# LightBox.net
KiCad netlist of a schematic drawn in EAGLE
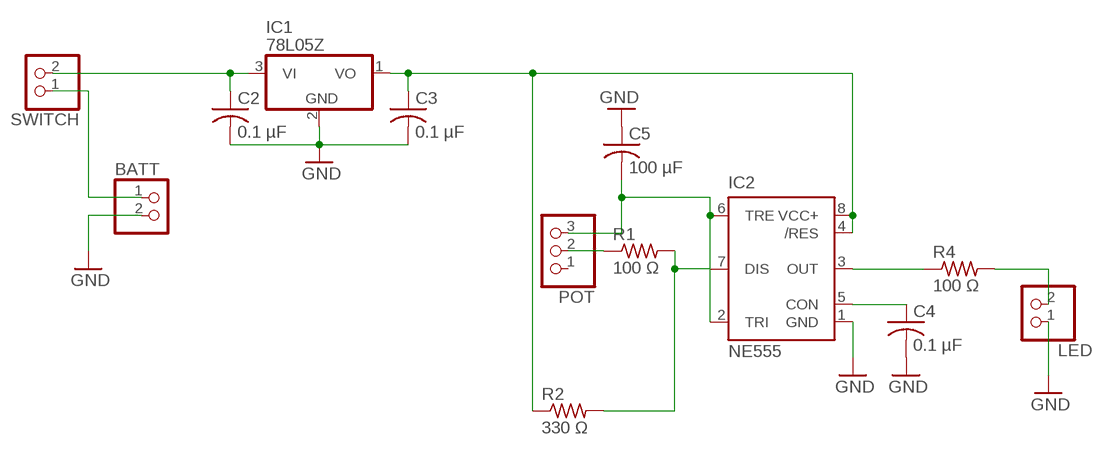
[diagram p0: schematic, sheet 1]

(export (version "E")
  (design (tool "Eeschema 10.0.6"))
  (components
    (comp (ref "BATT")
      (value "PINHD-1X2")
      (footprint "eagle-import:1X02")
      (libsource (lib "eagle-import") (part "PINHD-1X2"))
    )
    (comp (ref "C2")
      (value "0.1 µF")
      (footprint "eagle-import:C0805")
      (libsource (lib "eagle-import") (part "C-USC0805"))
    )
    (comp (ref "C3")
      (value "0.1 µF")
      (footprint "eagle-import:C0805")
      (libsource (lib "eagle-import") (part "C-USC0805"))
    )
    (comp (ref "C4")
      (value "0.1 µF")
      (footprint "eagle-import:C0805")
      (libsource (lib "eagle-import") (part "C-USC0805"))
    )
    (comp (ref "C5")
      (value "100 µF")
      (footprint "eagle-import:C025-024X044")
      (libsource (lib "eagle-import") (part "C-US025-024X044"))
    )
    (comp (ref "IC1")
      (value "78L05Z")
      (footprint "eagle-import:TO92")
      (libsource (lib "eagle-import") (part "78ZL05"))
    )
    (comp (ref "IC2")
      (value "NE555")
      (footprint "eagle-import:DIL-08")
      (fields (field (name "MF") "Arrow Electronics") (field (name "MPN") "NE555N"))
      (libsource (lib "eagle-import") (part "NE555"))
    )
    (comp (ref "LED")
      (value "PINHD-1X2")
      (footprint "eagle-import:1X02")
      (libsource (lib "eagle-import") (part "PINHD-1X2"))
    )
    (comp (ref "POT")
      (value "PINHD-1X3")
      (footprint "eagle-import:1X03")
      (libsource (lib "eagle-import") (part "PINHD-1X3"))
    )
    (comp (ref "R1")
      (value "100 Ω")
      (footprint "eagle-import:R0805")
      (libsource (lib "eagle-import") (part "R-US_R0805"))
    )
    (comp (ref "R2")
      (value "330 Ω")
      (footprint "eagle-import:R0805")
      (libsource (lib "eagle-import") (part "R-US_R0805"))
    )
    (comp (ref "R4")
      (value "100 Ω")
      (footprint "eagle-import:R0805")
      (libsource (lib "eagle-import") (part "R-US_R0805"))
    )
    (comp (ref "SWITCH")
      (value "PINHD-1X2")
      (footprint "eagle-import:1X02")
      (libsource (lib "eagle-import") (part "PINHD-1X2"))
    )
  )
  (nets
    (net (code "1") (name "GND") (class "Default")
      (node (ref "BATT") (pin "2") (pinfunction "2_2") (pintype "passive"))
      (node (ref "C2") (pin "2") (pinfunction "2_2") (pintype "passive"))
      (node (ref "C3") (pin "2") (pinfunction "2_2") (pintype "passive"))
      (node (ref "C4") (pin "2") (pinfunction "2_2") (pintype "passive"))
      (node (ref "C5") (pin "1") (pinfunction "1_1") (pintype "passive"))
      (node (ref "IC1") (pin "2") (pinfunction "GND_2") (pintype "passive"))
      (node (ref "IC2") (pin "1") (pinfunction "GND_1") (pintype "power_in"))
      (node (ref "LED") (pin "1") (pinfunction "1_1") (pintype "passive"))
    )
    (net (code "2") (name "Net-(BATT-Pad1)") (class "Default")
      (node (ref "BATT") (pin "1") (pinfunction "1_1") (pintype "passive"))
      (node (ref "SWITCH") (pin "1") (pinfunction "1_1") (pintype "passive"))
    )
    (net (code "3") (name "Net-(IC1-VI)") (class "Default")
      (node (ref "C2") (pin "1") (pinfunction "1_1") (pintype "passive"))
      (node (ref "IC1") (pin "3") (pinfunction "VI_3") (pintype "input"))
      (node (ref "SWITCH") (pin "2") (pinfunction "2_2") (pintype "passive"))
    )
    (net (code "4") (name "Net-(IC1-VO)") (class "Default")
      (node (ref "C3") (pin "1") (pinfunction "1_1") (pintype "passive"))
      (node (ref "IC1") (pin "1") (pinfunction "VO_1") (pintype "passive"))
      (node (ref "IC2") (pin "4") (pinfunction "/RES_4") (pintype "input"))
      (node (ref "IC2") (pin "8") (pinfunction "VCC+_8") (pintype "power_in"))
      (node (ref "R2") (pin "1") (pinfunction "1_1") (pintype "passive"))
    )
    (net (code "5") (name "Net-(IC2-CON)") (class "Default")
      (node (ref "C4") (pin "1") (pinfunction "1_1") (pintype "passive"))
      (node (ref "IC2") (pin "5") (pinfunction "CON_5") (pintype "input"))
    )
    (net (code "6") (name "Net-(IC2-DIS)") (class "Default")
      (node (ref "IC2") (pin "7") (pinfunction "DIS_7") (pintype "input"))
      (node (ref "R1") (pin "2") (pinfunction "2_2") (pintype "passive"))
      (node (ref "R2") (pin "2") (pinfunction "2_2") (pintype "passive"))
    )
    (net (code "7") (name "Net-(IC2-OUT)") (class "Default")
      (node (ref "IC2") (pin "3") (pinfunction "OUT_3") (pintype "output"))
      (node (ref "R4") (pin "1") (pinfunction "1_1") (pintype "passive"))
    )
    (net (code "8") (name "Net-(IC2-TRE)") (class "Default")
      (node (ref "C5") (pin "2") (pinfunction "2_2") (pintype "passive"))
      (node (ref "IC2") (pin "2") (pinfunction "TRI_2") (pintype "input"))
      (node (ref "IC2") (pin "6") (pinfunction "TRE_6") (pintype "input"))
      (node (ref "POT") (pin "3") (pinfunction "3_3") (pintype "passive"))
    )
    (net (code "9") (name "Net-(LED-Pad2)") (class "Default")
      (node (ref "LED") (pin "2") (pinfunction "2_2") (pintype "passive"))
      (node (ref "R4") (pin "2") (pinfunction "2_2") (pintype "passive"))
    )
    (net (code "10") (name "Net-(POT-Pad2)") (class "Default")
      (node (ref "POT") (pin "2") (pinfunction "2_2") (pintype "passive"))
      (node (ref "R1") (pin "1") (pinfunction "1_1") (pintype "passive"))
    )
    (net (code "11") (name "unconnected-(POT-Pad1)") (class "Default")
      (node (ref "POT") (pin "1") (pinfunction "1_1") (pintype "passive"))
    )
  )
)
